# TSOC_NEOLED_R0_1.net
KiCad netlist of a schematic drawn in EAGLE
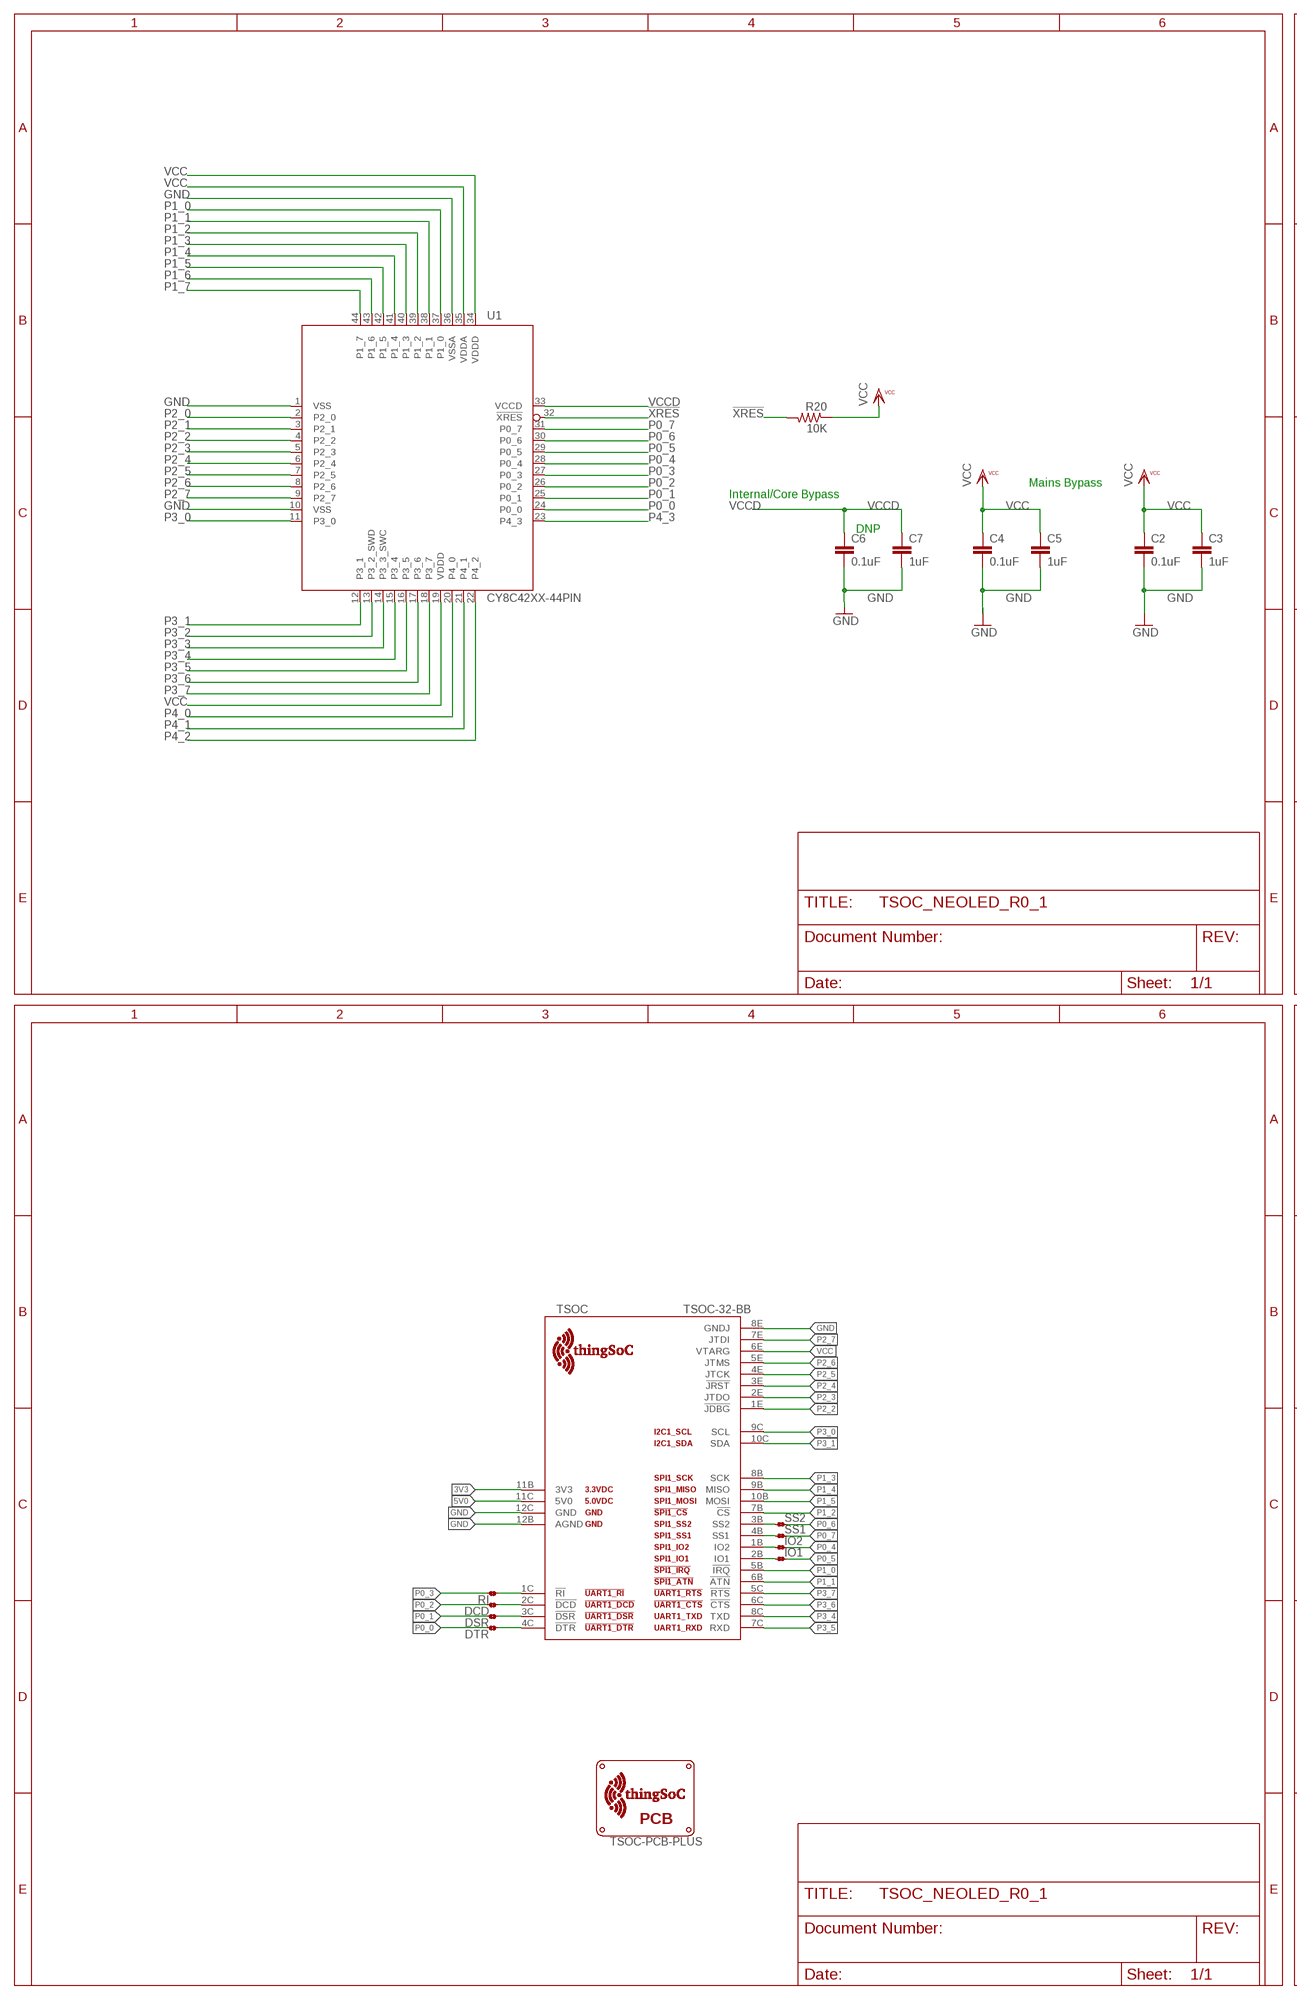
[diagram p0: schematic, sheet 1, part 1 of 2]
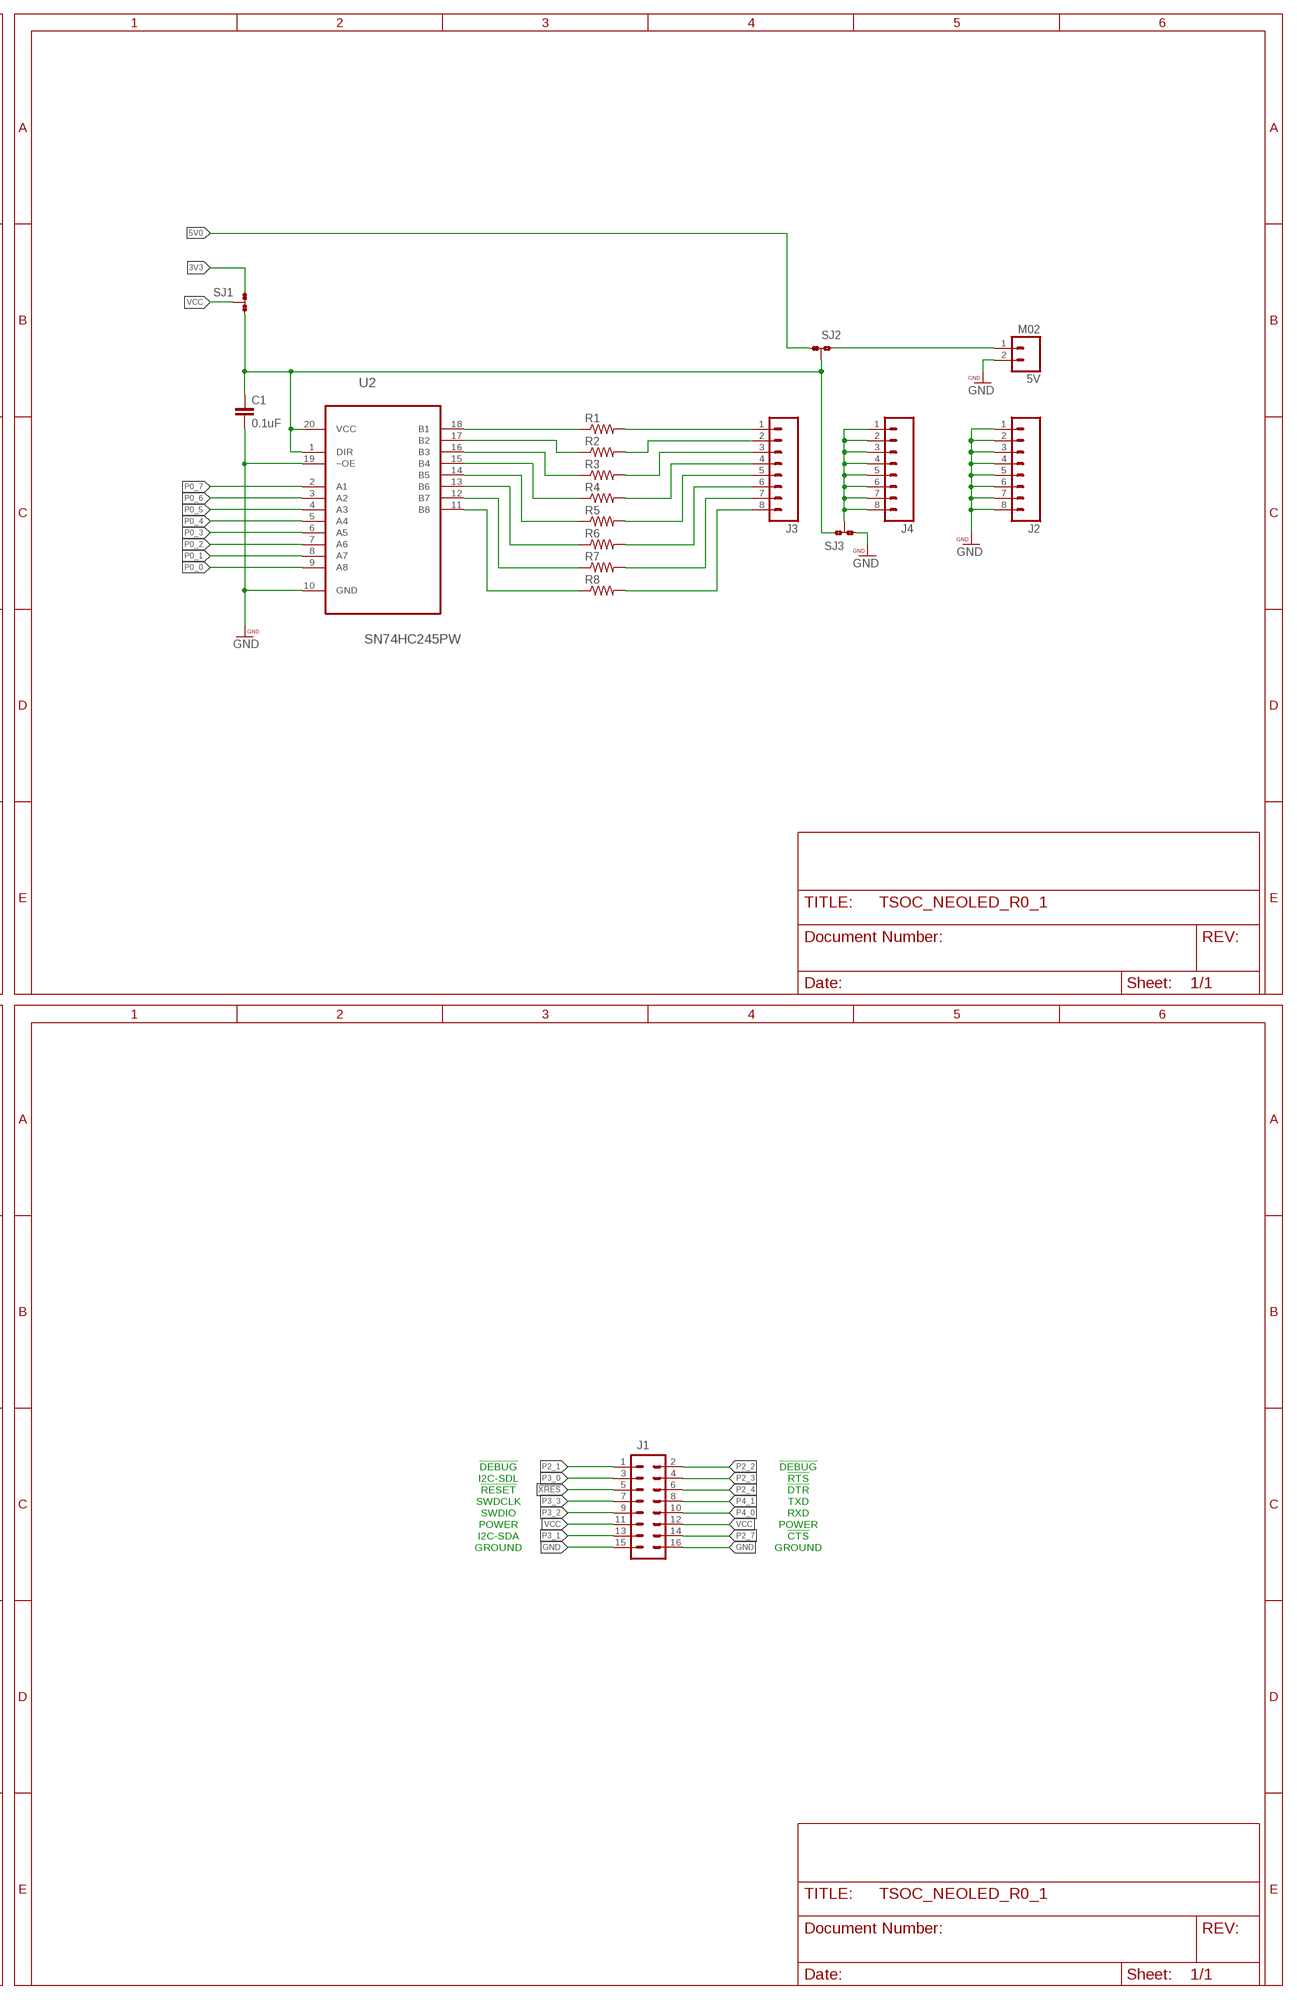
[diagram p1: schematic, sheet 1, part 2 of 2]

(export (version "E")
  (design (tool "Eeschema 10.0.6"))
  (components
    (comp (ref "5V")
      (value "M02")
      (footprint "eagle-import:1X02")
      (libsource (lib "eagle-import") (part "M02"))
    )
    (comp (ref "C1")
      (value "0.1uF")
      (footprint "eagle-import:0603-CAP")
      (libsource (lib "eagle-import") (part "CAP0603-CAP"))
    )
    (comp (ref "C2")
      (value "0.1uF")
      (footprint "eagle-import:0603-CAP")
      (libsource (lib "eagle-import") (part "CAP0603-CAP"))
    )
    (comp (ref "C3")
      (value "1uF")
      (footprint "eagle-import:0603-CAP")
      (libsource (lib "eagle-import") (part "CAP0603-CAP"))
    )
    (comp (ref "C4")
      (value "0.1uF")
      (footprint "eagle-import:0603-CAP")
      (libsource (lib "eagle-import") (part "CAP0603-CAP"))
    )
    (comp (ref "C5")
      (value "1uF")
      (footprint "eagle-import:0603-CAP")
      (libsource (lib "eagle-import") (part "CAP0603-CAP"))
    )
    (comp (ref "C6")
      (value "0.1uF")
      (footprint "eagle-import:0603-CAP")
      (libsource (lib "eagle-import") (part "CAP0603-CAP"))
    )
    (comp (ref "C7")
      (value "1uF")
      (footprint "eagle-import:0603-CAP")
      (libsource (lib "eagle-import") (part "CAP0603-CAP"))
    )
    (comp (ref "DCD")
      (value "JMP-2-NO")
      (footprint "eagle-import:JMP-2-NO")
      (libsource (lib "eagle-import") (part "JMP-2-NO"))
    )
    (comp (ref "DSR")
      (value "JMP-2-NO")
      (footprint "eagle-import:JMP-2-NO")
      (libsource (lib "eagle-import") (part "JMP-2-NO"))
    )
    (comp (ref "DTR")
      (value "JMP-2-NO")
      (footprint "eagle-import:JMP-2-NO")
      (libsource (lib "eagle-import") (part "JMP-2-NO"))
    )
    (comp (ref "IO1")
      (value "JMP-2-NO")
      (footprint "eagle-import:JMP-2-NO")
      (libsource (lib "eagle-import") (part "JMP-2-NO"))
    )
    (comp (ref "IO2")
      (value "JMP-2-NO")
      (footprint "eagle-import:JMP-2-NO")
      (libsource (lib "eagle-import") (part "JMP-2-NO"))
    )
    (comp (ref "J1")
      (value "M08X2")
      (footprint "eagle-import:2X8")
      (libsource (lib "eagle-import") (part "M08X2"))
    )
    (comp (ref "J2")
      (value "M08")
      (footprint "eagle-import:1X08_ROUND")
      (libsource (lib "eagle-import") (part "M08"))
    )
    (comp (ref "J3")
      (value "M08")
      (footprint "eagle-import:1X08_ROUND")
      (libsource (lib "eagle-import") (part "M08"))
    )
    (comp (ref "J4")
      (value "M08")
      (footprint "eagle-import:1X08_ROUND")
      (libsource (lib "eagle-import") (part "M08"))
    )
    (comp (ref "R1")
      (value "RESISTOR0603-RES")
      (footprint "eagle-import:0603-RES")
      (libsource (lib "eagle-import") (part "RESISTOR0603-RES"))
    )
    (comp (ref "R2")
      (value "RESISTOR0603-RES")
      (footprint "eagle-import:0603-RES")
      (libsource (lib "eagle-import") (part "RESISTOR0603-RES"))
    )
    (comp (ref "R3")
      (value "RESISTOR0603-RES")
      (footprint "eagle-import:0603-RES")
      (libsource (lib "eagle-import") (part "RESISTOR0603-RES"))
    )
    (comp (ref "R4")
      (value "RESISTOR0603-RES")
      (footprint "eagle-import:0603-RES")
      (libsource (lib "eagle-import") (part "RESISTOR0603-RES"))
    )
    (comp (ref "R5")
      (value "RESISTOR0603-RES")
      (footprint "eagle-import:0603-RES")
      (libsource (lib "eagle-import") (part "RESISTOR0603-RES"))
    )
    (comp (ref "R6")
      (value "RESISTOR0603-RES")
      (footprint "eagle-import:0603-RES")
      (libsource (lib "eagle-import") (part "RESISTOR0603-RES"))
    )
    (comp (ref "R7")
      (value "RESISTOR0603-RES")
      (footprint "eagle-import:0603-RES")
      (libsource (lib "eagle-import") (part "RESISTOR0603-RES"))
    )
    (comp (ref "R8")
      (value "RESISTOR0603-RES")
      (footprint "eagle-import:0603-RES")
      (libsource (lib "eagle-import") (part "RESISTOR0603-RES"))
    )
    (comp (ref "R20")
      (value "10K")
      (footprint "eagle-import:0603-RES")
      (libsource (lib "eagle-import") (part "RESISTOR_SFE0603-RES"))
    )
    (comp (ref "RI")
      (value "JMP-2-NO")
      (footprint "eagle-import:JMP-2-NO")
      (libsource (lib "eagle-import") (part "JMP-2-NO"))
    )
    (comp (ref "SJ1")
      (value "JMP-3-1_2")
      (footprint "eagle-import:JMP-3-1_2")
      (libsource (lib "eagle-import") (part "JMP-3-1_2"))
    )
    (comp (ref "SJ2")
      (value "JMP-3-1_2")
      (footprint "eagle-import:JMP-3-1_2")
      (libsource (lib "eagle-import") (part "JMP-3-1_2"))
    )
    (comp (ref "SJ3")
      (value "JMP-3-1_2")
      (footprint "eagle-import:JMP-3-1_2")
      (libsource (lib "eagle-import") (part "JMP-3-1_2"))
    )
    (comp (ref "SS1")
      (value "JMP-2-NO")
      (footprint "eagle-import:JMP-2-NO")
      (libsource (lib "eagle-import") (part "JMP-2-NO"))
    )
    (comp (ref "SS2")
      (value "JMP-2-NO")
      (footprint "eagle-import:JMP-2-NO")
      (libsource (lib "eagle-import") (part "JMP-2-NO"))
    )
    (comp (ref "TSOC")
      (value "TSOC-32-BB")
      (footprint "eagle-import:TSOC-BB-S32")
      (libsource (lib "eagle-import") (part "TSOC-32-BB"))
    )
    (comp (ref "U$3")
      (value "TSOC-PCB-PLUS")
      (footprint "eagle-import:TSOC-BB-BRD-PLUS")
      (libsource (lib "eagle-import") (part "TSOC-PCB-PLUS"))
    )
    (comp (ref "U1")
      (value "CY8C42XX-44PIN")
      (footprint "eagle-import:TQFP-10X10-44")
      (libsource (lib "eagle-import") (part "CY8C42XX-44PIN"))
    )
    (comp (ref "U2")
      (value "SN74HC245PW")
      (footprint "eagle-import:SOP65P640X120-20N")
      (libsource (lib "eagle-import") (part "SN74HC245PW"))
    )
  )
  (nets
    (net (code "1") (name "/P1_6") (class "Default")
      (node (ref "U1") (pin "43") (pinfunction "P1_6_43") (pintype "bidirectional"))
    )
    (net (code "2") (name "/P1_7") (class "Default")
      (node (ref "U1") (pin "44") (pinfunction "P1_7_44") (pintype "bidirectional"))
    )
    (net (code "3") (name "/P2_0") (class "Default")
      (node (ref "U1") (pin "2") (pinfunction "P2_0_2") (pintype "bidirectional"))
    )
    (net (code "4") (name "/P4_2") (class "Default")
      (node (ref "U1") (pin "22") (pinfunction "P4_2_22") (pintype "bidirectional"))
    )
    (net (code "5") (name "/P4_3") (class "Default")
      (node (ref "U1") (pin "23") (pinfunction "P4_3_23") (pintype "bidirectional"))
    )
    (net (code "6") (name "/VCCD") (class "Default")
      (node (ref "C6") (pin "1") (pinfunction "1_1") (pintype "passive"))
      (node (ref "C7") (pin "1") (pinfunction "1_1") (pintype "passive"))
      (node (ref "U1") (pin "33") (pinfunction "VCCD_33") (pintype "bidirectional"))
    )
    (net (code "7") (name "/~{XRES}") (class "Default")
      (node (ref "J1") (pin "5") (pinfunction "5_5") (pintype "passive"))
      (node (ref "R20") (pin "2") (pinfunction "2_2") (pintype "passive"))
      (node (ref "U1") (pin "32") (pinfunction "~{XRES}_32") (pintype "bidirectional"))
    )
    (net (code "8") (name "3V3") (class "Default")
      (node (ref "SJ1") (pin "1") (pinfunction "1_1") (pintype "passive"))
      (node (ref "TSOC") (pin "11B") (pinfunction "3V3_11B") (pintype "bidirectional"))
    )
    (net (code "9") (name "5V0") (class "Default")
      (node (ref "SJ2") (pin "1") (pinfunction "1_1") (pintype "passive"))
      (node (ref "TSOC") (pin "11C") (pinfunction "5V0_11C") (pintype "bidirectional"))
    )
    (net (code "10") (name "GND") (class "Default")
      (node (ref "5V") (pin "2") (pinfunction "2_2") (pintype "passive"))
      (node (ref "C1") (pin "2") (pinfunction "2_2") (pintype "passive"))
      (node (ref "C2") (pin "2") (pinfunction "2_2") (pintype "passive"))
      (node (ref "C3") (pin "2") (pinfunction "2_2") (pintype "passive"))
      (node (ref "C4") (pin "2") (pinfunction "2_2") (pintype "passive"))
      (node (ref "C5") (pin "2") (pinfunction "2_2") (pintype "passive"))
      (node (ref "C6") (pin "2") (pinfunction "2_2") (pintype "passive"))
      (node (ref "C7") (pin "2") (pinfunction "2_2") (pintype "passive"))
      (node (ref "J1") (pin "15") (pinfunction "15_15") (pintype "passive"))
      (node (ref "J1") (pin "16") (pinfunction "16_16") (pintype "passive"))
      (node (ref "J2") (pin "1") (pinfunction "1_1") (pintype "passive"))
      (node (ref "J2") (pin "2") (pinfunction "2_2") (pintype "passive"))
      (node (ref "J2") (pin "3") (pinfunction "3_3") (pintype "passive"))
      (node (ref "J2") (pin "4") (pinfunction "4_4") (pintype "passive"))
      (node (ref "J2") (pin "5") (pinfunction "5_5") (pintype "passive"))
      (node (ref "J2") (pin "6") (pinfunction "6_6") (pintype "passive"))
      (node (ref "J2") (pin "7") (pinfunction "7_7") (pintype "passive"))
      (node (ref "J2") (pin "8") (pinfunction "8_8") (pintype "passive"))
      (node (ref "SJ3") (pin "1") (pinfunction "1_1") (pintype "passive"))
      (node (ref "TSOC") (pin "12B") (pinfunction "AGND_12B") (pintype "bidirectional"))
      (node (ref "TSOC") (pin "12C") (pinfunction "GND_12C") (pintype "bidirectional"))
      (node (ref "TSOC") (pin "8E") (pinfunction "GNDJ_8E") (pintype "bidirectional"))
      (node (ref "U1") (pin "1") (pinfunction "VSS_1") (pintype "bidirectional"))
      (node (ref "U1") (pin "10") (pinfunction "VSS_10") (pintype "bidirectional"))
      (node (ref "U1") (pin "36") (pinfunction "VSSA_36") (pintype "bidirectional"))
      (node (ref "U2") (pin "10") (pinfunction "GND_10") (pintype "input"))
      (node (ref "U2") (pin "19") (pinfunction "~{OE}_19") (pintype "input"))
    )
    (net (code "11") (name "Net-(5V-Pad1)") (class "Default")
      (node (ref "5V") (pin "1") (pinfunction "1_1") (pintype "passive"))
      (node (ref "SJ2") (pin "3") (pinfunction "3_3") (pintype "passive"))
    )
    (net (code "12") (name "Net-(J3-Pad1)") (class "Default")
      (node (ref "J3") (pin "1") (pinfunction "1_1") (pintype "passive"))
      (node (ref "R1") (pin "2") (pinfunction "2_2") (pintype "passive"))
    )
    (net (code "13") (name "Net-(J3-Pad2)") (class "Default")
      (node (ref "J3") (pin "2") (pinfunction "2_2") (pintype "passive"))
      (node (ref "R2") (pin "2") (pinfunction "2_2") (pintype "passive"))
    )
    (net (code "14") (name "Net-(J3-Pad3)") (class "Default")
      (node (ref "J3") (pin "3") (pinfunction "3_3") (pintype "passive"))
      (node (ref "R3") (pin "2") (pinfunction "2_2") (pintype "passive"))
    )
    (net (code "15") (name "Net-(J3-Pad4)") (class "Default")
      (node (ref "J3") (pin "4") (pinfunction "4_4") (pintype "passive"))
      (node (ref "R4") (pin "2") (pinfunction "2_2") (pintype "passive"))
    )
    (net (code "16") (name "Net-(J3-Pad5)") (class "Default")
      (node (ref "J3") (pin "5") (pinfunction "5_5") (pintype "passive"))
      (node (ref "R5") (pin "2") (pinfunction "2_2") (pintype "passive"))
    )
    (net (code "17") (name "Net-(J3-Pad6)") (class "Default")
      (node (ref "J3") (pin "6") (pinfunction "6_6") (pintype "passive"))
      (node (ref "R6") (pin "2") (pinfunction "2_2") (pintype "passive"))
    )
    (net (code "18") (name "Net-(J3-Pad7)") (class "Default")
      (node (ref "J3") (pin "7") (pinfunction "7_7") (pintype "passive"))
      (node (ref "R7") (pin "2") (pinfunction "2_2") (pintype "passive"))
    )
    (net (code "19") (name "Net-(J3-Pad8)") (class "Default")
      (node (ref "J3") (pin "8") (pinfunction "8_8") (pintype "passive"))
      (node (ref "R8") (pin "2") (pinfunction "2_2") (pintype "passive"))
    )
    (net (code "20") (name "Net-(J4-Pad1)") (class "Default")
      (node (ref "J4") (pin "1") (pinfunction "1_1") (pintype "passive"))
      (node (ref "J4") (pin "2") (pinfunction "2_2") (pintype "passive"))
      (node (ref "J4") (pin "3") (pinfunction "3_3") (pintype "passive"))
      (node (ref "J4") (pin "4") (pinfunction "4_4") (pintype "passive"))
      (node (ref "J4") (pin "5") (pinfunction "5_5") (pintype "passive"))
      (node (ref "J4") (pin "6") (pinfunction "6_6") (pintype "passive"))
      (node (ref "J4") (pin "7") (pinfunction "7_7") (pintype "passive"))
      (node (ref "J4") (pin "8") (pinfunction "8_8") (pintype "passive"))
      (node (ref "SJ3") (pin "2") (pinfunction "2_2") (pintype "passive"))
    )
    (net (code "21") (name "Net-(TSOC-IO1)") (class "Default")
      (node (ref "IO1") (pin "1") (pinfunction "1_1") (pintype "passive"))
      (node (ref "TSOC") (pin "2B") (pinfunction "IO1_2B") (pintype "bidirectional"))
    )
    (net (code "22") (name "Net-(TSOC-IO2)") (class "Default")
      (node (ref "IO2") (pin "1") (pinfunction "1_1") (pintype "passive"))
      (node (ref "TSOC") (pin "1B") (pinfunction "IO2_1B") (pintype "bidirectional"))
    )
    (net (code "23") (name "Net-(TSOC-SS1)") (class "Default")
      (node (ref "SS1") (pin "1") (pinfunction "1_1") (pintype "passive"))
      (node (ref "TSOC") (pin "4B") (pinfunction "SS1_4B") (pintype "bidirectional"))
    )
    (net (code "24") (name "Net-(TSOC-SS2)") (class "Default")
      (node (ref "SS2") (pin "1") (pinfunction "1_1") (pintype "passive"))
      (node (ref "TSOC") (pin "3B") (pinfunction "SS2_3B") (pintype "bidirectional"))
    )
    (net (code "25") (name "Net-(TSOC-~{DCD})") (class "Default")
      (node (ref "DCD") (pin "1") (pinfunction "1_1") (pintype "passive"))
      (node (ref "TSOC") (pin "2C") (pinfunction "~{DCD}_2C") (pintype "bidirectional"))
    )
    (net (code "26") (name "Net-(TSOC-~{DSR})") (class "Default")
      (node (ref "DSR") (pin "1") (pinfunction "1_1") (pintype "passive"))
      (node (ref "TSOC") (pin "3C") (pinfunction "~{DSR}_3C") (pintype "bidirectional"))
    )
    (net (code "27") (name "Net-(TSOC-~{DTR})") (class "Default")
      (node (ref "DTR") (pin "1") (pinfunction "1_1") (pintype "passive"))
      (node (ref "TSOC") (pin "4C") (pinfunction "~{DTR}_4C") (pintype "bidirectional"))
    )
    (net (code "28") (name "Net-(TSOC-~{RI})") (class "Default")
      (node (ref "RI") (pin "1") (pinfunction "1_1") (pintype "passive"))
      (node (ref "TSOC") (pin "1C") (pinfunction "~{RI}_1C") (pintype "bidirectional"))
    )
    (net (code "29") (name "Net-(U2-B1)") (class "Default")
      (node (ref "R1") (pin "1") (pinfunction "1_1") (pintype "passive"))
      (node (ref "U2") (pin "18") (pinfunction "B1_18") (pintype "bidirectional"))
    )
    (net (code "30") (name "Net-(U2-B2)") (class "Default")
      (node (ref "R2") (pin "1") (pinfunction "1_1") (pintype "passive"))
      (node (ref "U2") (pin "17") (pinfunction "B2_17") (pintype "bidirectional"))
    )
    (net (code "31") (name "Net-(U2-B3)") (class "Default")
      (node (ref "R3") (pin "1") (pinfunction "1_1") (pintype "passive"))
      (node (ref "U2") (pin "16") (pinfunction "B3_16") (pintype "bidirectional"))
    )
    (net (code "32") (name "Net-(U2-B4)") (class "Default")
      (node (ref "R4") (pin "1") (pinfunction "1_1") (pintype "passive"))
      (node (ref "U2") (pin "15") (pinfunction "B4_15") (pintype "bidirectional"))
    )
    (net (code "33") (name "Net-(U2-B5)") (class "Default")
      (node (ref "R5") (pin "1") (pinfunction "1_1") (pintype "passive"))
      (node (ref "U2") (pin "14") (pinfunction "B5_14") (pintype "bidirectional"))
    )
    (net (code "34") (name "Net-(U2-B6)") (class "Default")
      (node (ref "R6") (pin "1") (pinfunction "1_1") (pintype "passive"))
      (node (ref "U2") (pin "13") (pinfunction "B6_13") (pintype "bidirectional"))
    )
    (net (code "35") (name "Net-(U2-B7)") (class "Default")
      (node (ref "R7") (pin "1") (pinfunction "1_1") (pintype "passive"))
      (node (ref "U2") (pin "12") (pinfunction "B7_12") (pintype "bidirectional"))
    )
    (net (code "36") (name "Net-(U2-B8)") (class "Default")
      (node (ref "R8") (pin "1") (pinfunction "1_1") (pintype "passive"))
      (node (ref "U2") (pin "11") (pinfunction "B8_11") (pintype "bidirectional"))
    )
    (net (code "37") (name "Net-(U2-DIR)") (class "Default")
      (node (ref "C1") (pin "1") (pinfunction "1_1") (pintype "passive"))
      (node (ref "SJ1") (pin "3") (pinfunction "3_3") (pintype "passive"))
      (node (ref "SJ2") (pin "2") (pinfunction "2_2") (pintype "passive"))
      (node (ref "SJ3") (pin "3") (pinfunction "3_3") (pintype "passive"))
      (node (ref "U2") (pin "1") (pinfunction "DIR_1") (pintype "input"))
      (node (ref "U2") (pin "20") (pinfunction "VCC_20") (pintype "power_in"))
    )
    (net (code "38") (name "P0_0") (class "Default")
      (node (ref "DTR") (pin "2") (pinfunction "2_2") (pintype "passive"))
      (node (ref "U1") (pin "24") (pinfunction "P0_0_24") (pintype "bidirectional"))
      (node (ref "U2") (pin "9") (pinfunction "A8_9") (pintype "bidirectional"))
    )
    (net (code "39") (name "P0_1") (class "Default")
      (node (ref "DSR") (pin "2") (pinfunction "2_2") (pintype "passive"))
      (node (ref "U1") (pin "25") (pinfunction "P0_1_25") (pintype "bidirectional"))
      (node (ref "U2") (pin "8") (pinfunction "A7_8") (pintype "bidirectional"))
    )
    (net (code "40") (name "P0_2") (class "Default")
      (node (ref "DCD") (pin "2") (pinfunction "2_2") (pintype "passive"))
      (node (ref "U1") (pin "26") (pinfunction "P0_2_26") (pintype "input"))
      (node (ref "U2") (pin "7") (pinfunction "A6_7") (pintype "bidirectional"))
    )
    (net (code "41") (name "P0_3") (class "Default")
      (node (ref "RI") (pin "2") (pinfunction "2_2") (pintype "passive"))
      (node (ref "U1") (pin "27") (pinfunction "P0_3_27") (pintype "bidirectional"))
      (node (ref "U2") (pin "6") (pinfunction "A5_6") (pintype "bidirectional"))
    )
    (net (code "42") (name "P0_4") (class "Default")
      (node (ref "IO2") (pin "2") (pinfunction "2_2") (pintype "passive"))
      (node (ref "U1") (pin "28") (pinfunction "P0_4_28") (pintype "bidirectional"))
      (node (ref "U2") (pin "5") (pinfunction "A4_5") (pintype "bidirectional"))
    )
    (net (code "43") (name "P0_5") (class "Default")
      (node (ref "IO1") (pin "2") (pinfunction "2_2") (pintype "passive"))
      (node (ref "U1") (pin "29") (pinfunction "P0_5_29") (pintype "bidirectional"))
      (node (ref "U2") (pin "4") (pinfunction "A3_4") (pintype "bidirectional"))
    )
    (net (code "44") (name "P0_6") (class "Default")
      (node (ref "SS2") (pin "2") (pinfunction "2_2") (pintype "passive"))
      (node (ref "U1") (pin "30") (pinfunction "P0_6_30") (pintype "power_in"))
      (node (ref "U2") (pin "3") (pinfunction "A2_3") (pintype "bidirectional"))
    )
    (net (code "45") (name "P0_7") (class "Default")
      (node (ref "SS1") (pin "2") (pinfunction "2_2") (pintype "passive"))
      (node (ref "U1") (pin "31") (pinfunction "P0_7_31") (pintype "bidirectional"))
      (node (ref "U2") (pin "2") (pinfunction "A1_2") (pintype "bidirectional"))
    )
    (net (code "46") (name "P1_0") (class "Default")
      (node (ref "TSOC") (pin "5B") (pinfunction "~{IRQ}_5B") (pintype "bidirectional"))
      (node (ref "U1") (pin "37") (pinfunction "P1_0_37") (pintype "bidirectional"))
    )
    (net (code "47") (name "P1_1") (class "Default")
      (node (ref "TSOC") (pin "6B") (pinfunction "~{ATN}_6B") (pintype "bidirectional"))
      (node (ref "U1") (pin "38") (pinfunction "P1_1_38") (pintype "bidirectional"))
    )
    (net (code "48") (name "P1_2") (class "Default")
      (node (ref "TSOC") (pin "7B") (pinfunction "~{CS}_7B") (pintype "bidirectional"))
      (node (ref "U1") (pin "39") (pinfunction "P1_2_39") (pintype "power_in"))
    )
    (net (code "49") (name "P1_3") (class "Default")
      (node (ref "TSOC") (pin "8B") (pinfunction "SCK_8B") (pintype "bidirectional"))
      (node (ref "U1") (pin "40") (pinfunction "P1_3_40") (pintype "bidirectional"))
    )
    (net (code "50") (name "P1_4") (class "Default")
      (node (ref "TSOC") (pin "9B") (pinfunction "MISO_9B") (pintype "bidirectional"))
      (node (ref "U1") (pin "41") (pinfunction "P1_4_41") (pintype "bidirectional"))
    )
    (net (code "51") (name "P1_5") (class "Default")
      (node (ref "TSOC") (pin "10B") (pinfunction "MOSI_10B") (pintype "bidirectional"))
      (node (ref "U1") (pin "42") (pinfunction "P1_5_42") (pintype "bidirectional"))
    )
    (net (code "52") (name "P2_1") (class "Default")
      (node (ref "J1") (pin "1") (pinfunction "1_1") (pintype "passive"))
      (node (ref "U1") (pin "3") (pinfunction "P2_1_3") (pintype "bidirectional"))
    )
    (net (code "53") (name "P2_2") (class "Default")
      (node (ref "J1") (pin "2") (pinfunction "2_2") (pintype "passive"))
      (node (ref "TSOC") (pin "1E") (pinfunction "~{JDBG}_1E") (pintype "bidirectional"))
      (node (ref "U1") (pin "4") (pinfunction "P2_2_4") (pintype "power_in"))
    )
    (net (code "54") (name "P2_3") (class "Default")
      (node (ref "J1") (pin "4") (pinfunction "4_4") (pintype "passive"))
      (node (ref "TSOC") (pin "2E") (pinfunction "JTDO_2E") (pintype "bidirectional"))
      (node (ref "U1") (pin "5") (pinfunction "P2_3_5") (pintype "bidirectional"))
    )
    (net (code "55") (name "P2_4") (class "Default")
      (node (ref "J1") (pin "6") (pinfunction "6_6") (pintype "passive"))
      (node (ref "TSOC") (pin "3E") (pinfunction "~{JRST}_3E") (pintype "bidirectional"))
      (node (ref "U1") (pin "6") (pinfunction "P2_4_6") (pintype "bidirectional"))
    )
    (net (code "56") (name "P2_5") (class "Default")
      (node (ref "TSOC") (pin "4E") (pinfunction "JTCK_4E") (pintype "bidirectional"))
      (node (ref "U1") (pin "7") (pinfunction "P2_5_7") (pintype "bidirectional"))
    )
    (net (code "57") (name "P2_6") (class "Default")
      (node (ref "TSOC") (pin "5E") (pinfunction "JTMS_5E") (pintype "bidirectional"))
      (node (ref "U1") (pin "8") (pinfunction "P2_6_8") (pintype "power_in"))
    )
    (net (code "58") (name "P2_7") (class "Default")
      (node (ref "J1") (pin "14") (pinfunction "14_14") (pintype "passive"))
      (node (ref "TSOC") (pin "7E") (pinfunction "JTDI_7E") (pintype "bidirectional"))
      (node (ref "U1") (pin "9") (pinfunction "P2_7_9") (pintype "bidirectional"))
    )
    (net (code "59") (name "P3_0") (class "Default")
      (node (ref "J1") (pin "3") (pinfunction "3_3") (pintype "passive"))
      (node (ref "TSOC") (pin "9C") (pinfunction "SCL_9C") (pintype "bidirectional"))
      (node (ref "U1") (pin "11") (pinfunction "P3_0_11") (pintype "bidirectional"))
    )
    (net (code "60") (name "P3_1") (class "Default")
      (node (ref "J1") (pin "13") (pinfunction "13_13") (pintype "passive"))
      (node (ref "TSOC") (pin "10C") (pinfunction "SDA_10C") (pintype "bidirectional"))
      (node (ref "U1") (pin "12") (pinfunction "P3_1_12") (pintype "bidirectional"))
    )
    (net (code "61") (name "P3_2") (class "Default")
      (node (ref "J1") (pin "9") (pinfunction "9_9") (pintype "passive"))
      (node (ref "U1") (pin "13") (pinfunction "P3_2_SWD_13") (pintype "bidirectional"))
    )
    (net (code "62") (name "P3_3") (class "Default")
      (node (ref "J1") (pin "7") (pinfunction "7_7") (pintype "passive"))
      (node (ref "U1") (pin "14") (pinfunction "P3_3_SWC_14") (pintype "bidirectional"))
    )
    (net (code "63") (name "P3_4") (class "Default")
      (node (ref "TSOC") (pin "8C") (pinfunction "TXD_8C") (pintype "bidirectional"))
      (node (ref "U1") (pin "15") (pinfunction "P3_4_15") (pintype "bidirectional"))
    )
    (net (code "64") (name "P3_5") (class "Default")
      (node (ref "TSOC") (pin "7C") (pinfunction "RXD_7C") (pintype "bidirectional"))
      (node (ref "U1") (pin "16") (pinfunction "P3_5_16") (pintype "bidirectional"))
    )
    (net (code "65") (name "P3_6") (class "Default")
      (node (ref "TSOC") (pin "6C") (pinfunction "~{CTS}_6C") (pintype "bidirectional"))
      (node (ref "U1") (pin "17") (pinfunction "P3_6_17") (pintype "power_in"))
    )
    (net (code "66") (name "P3_7") (class "Default")
      (node (ref "TSOC") (pin "5C") (pinfunction "~{RTS}_5C") (pintype "bidirectional"))
      (node (ref "U1") (pin "18") (pinfunction "P3_7_18") (pintype "bidirectional"))
    )
    (net (code "67") (name "P4_0") (class "Default")
      (node (ref "J1") (pin "10") (pinfunction "10_10") (pintype "passive"))
      (node (ref "U1") (pin "20") (pinfunction "P4_0_20") (pintype "bidirectional"))
    )
    (net (code "68") (name "P4_1") (class "Default")
      (node (ref "J1") (pin "8") (pinfunction "8_8") (pintype "passive"))
      (node (ref "U1") (pin "21") (pinfunction "P4_1_21") (pintype "bidirectional"))
    )
    (net (code "69") (name "VCC") (class "Default")
      (node (ref "C2") (pin "1") (pinfunction "1_1") (pintype "passive"))
      (node (ref "C3") (pin "1") (pinfunction "1_1") (pintype "passive"))
      (node (ref "C4") (pin "1") (pinfunction "1_1") (pintype "passive"))
      (node (ref "C5") (pin "1") (pinfunction "1_1") (pintype "passive"))
      (node (ref "J1") (pin "11") (pinfunction "11_11") (pintype "passive"))
      (node (ref "J1") (pin "12") (pinfunction "12_12") (pintype "passive"))
      (node (ref "R20") (pin "1") (pinfunction "1_1") (pintype "passive"))
      (node (ref "SJ1") (pin "2") (pinfunction "2_2") (pintype "passive"))
      (node (ref "TSOC") (pin "6E") (pinfunction "VTARG_6E") (pintype "bidirectional"))
      (node (ref "U1") (pin "19") (pinfunction "VDDD_19") (pintype "bidirectional"))
      (node (ref "U1") (pin "34") (pinfunction "VDDD_34") (pintype "bidirectional"))
      (node (ref "U1") (pin "35") (pinfunction "VDDA_35") (pintype "bidirectional"))
    )
  )
)
